# SCH_lab05_2021-12-17_1.net
KiCad netlist of a schematic drawn in EasyEDA
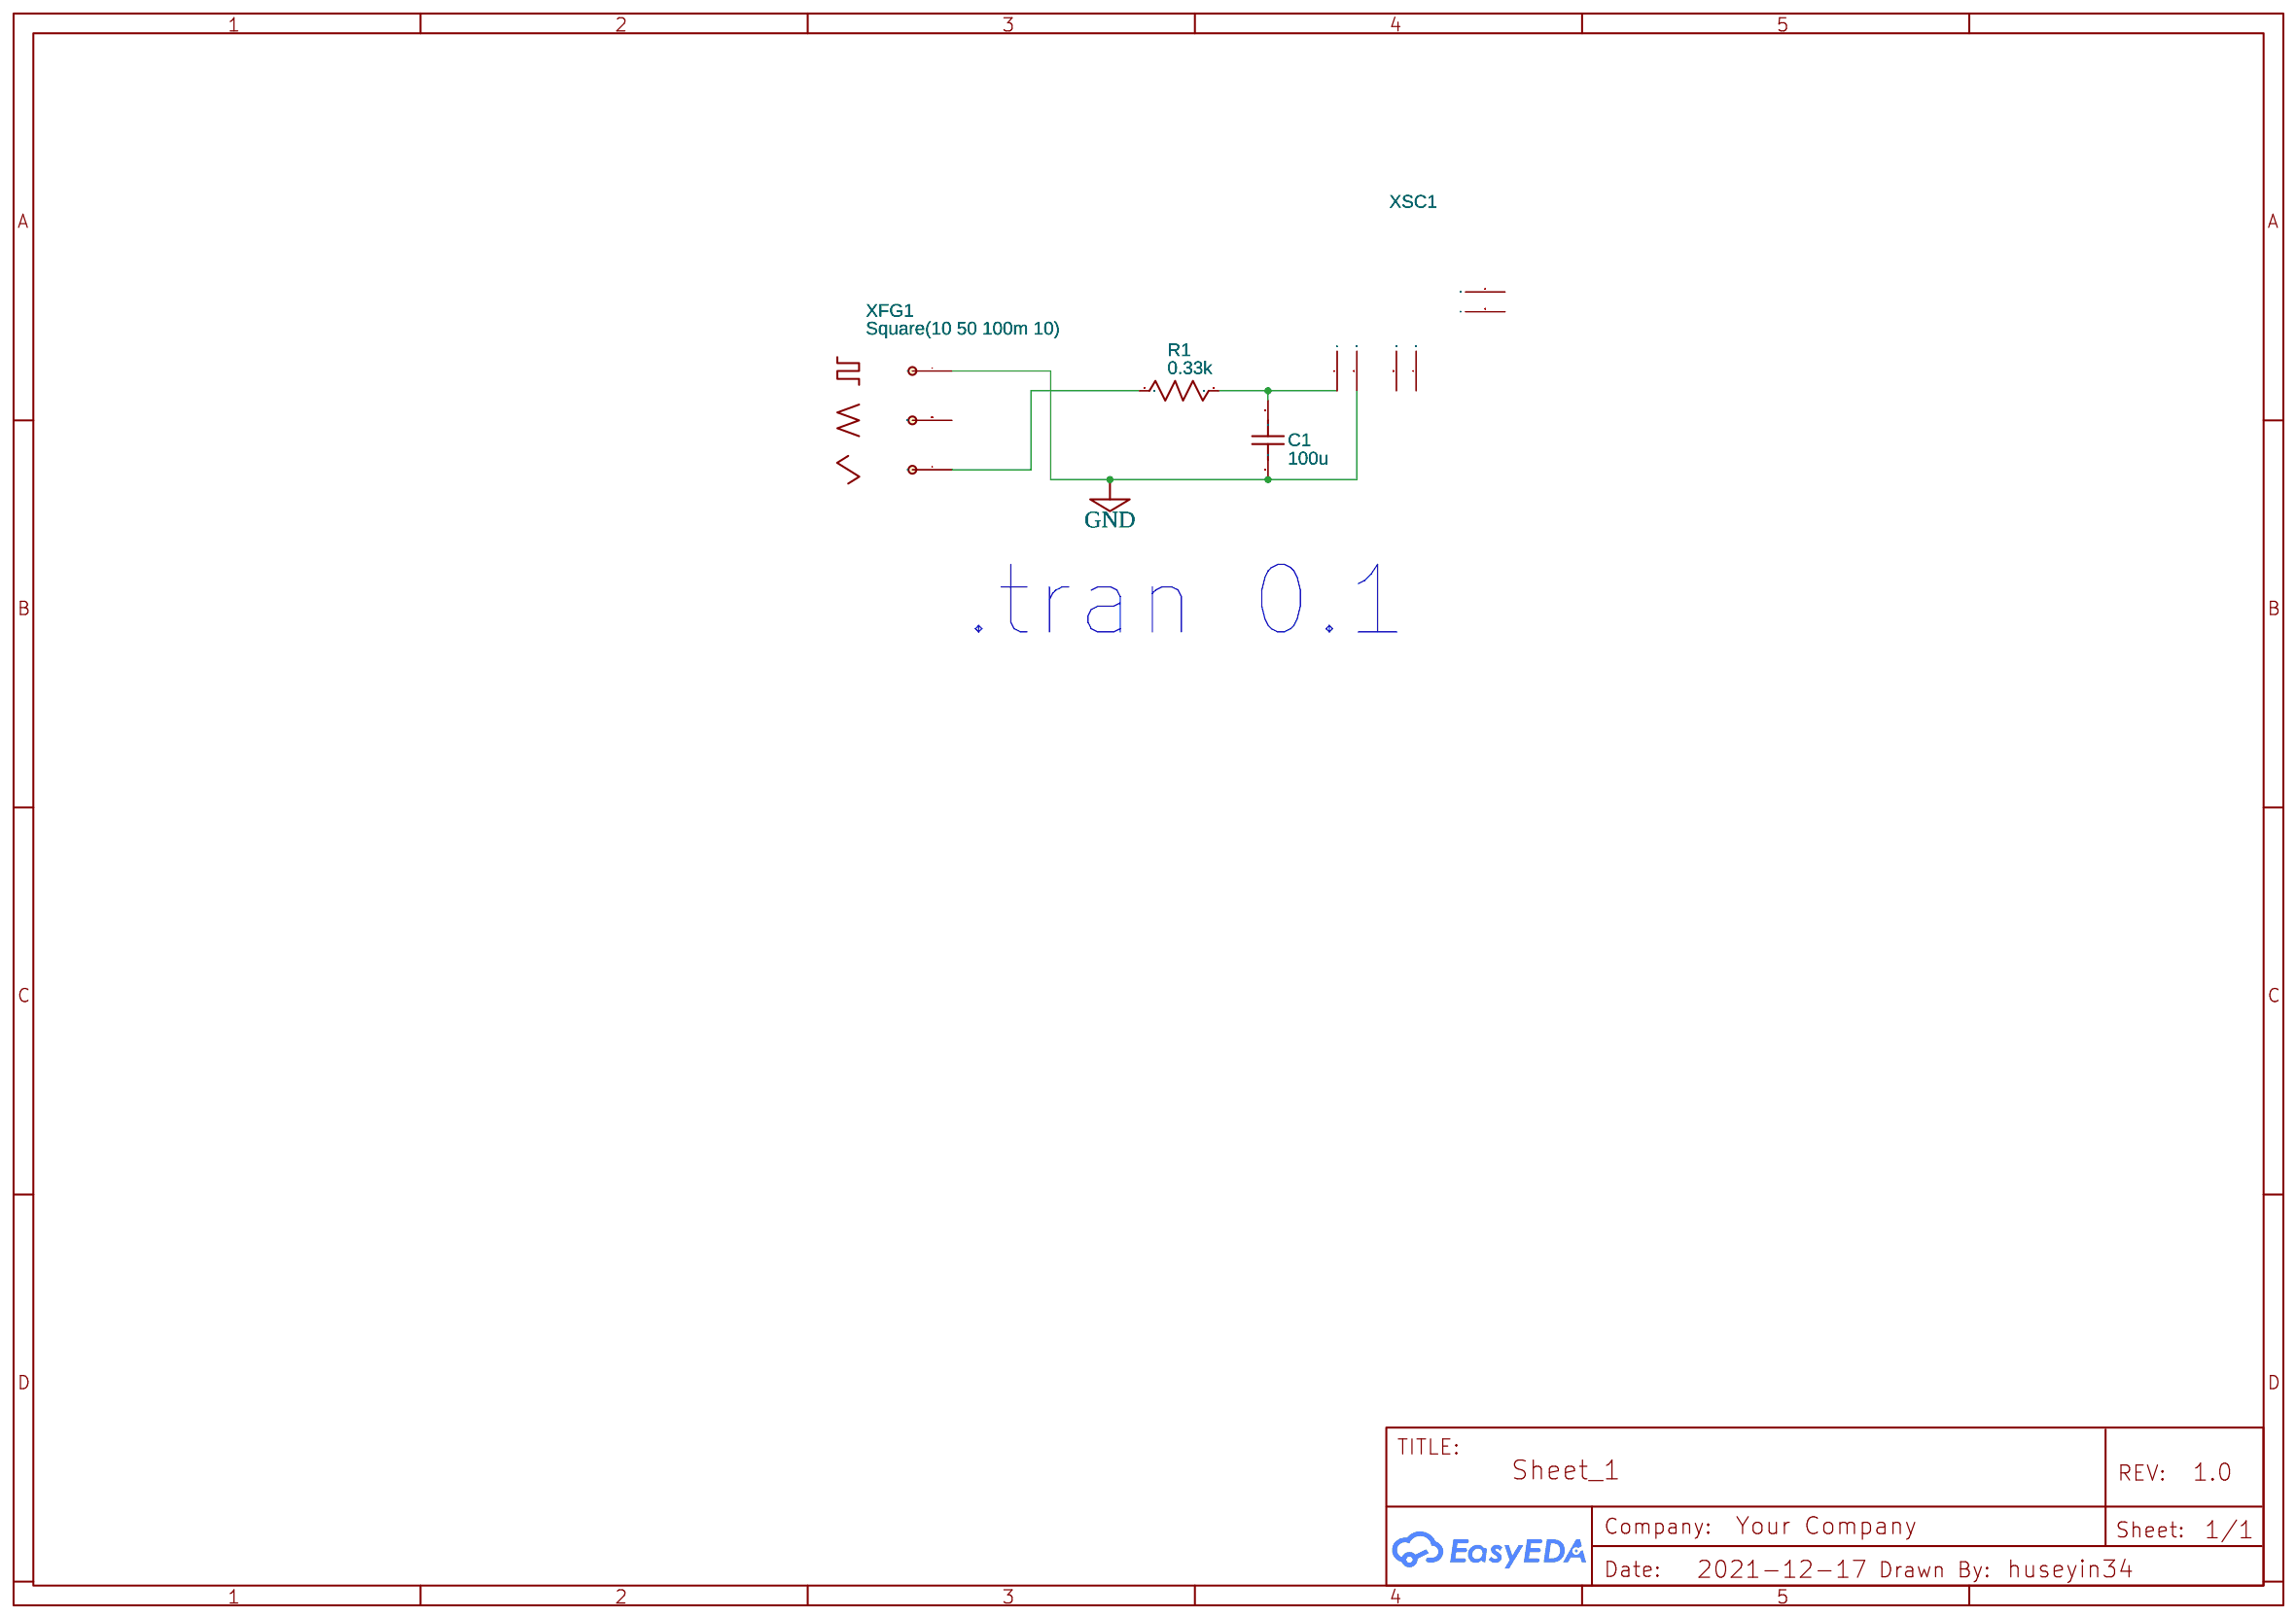
[diagram p0: Sheet_1]
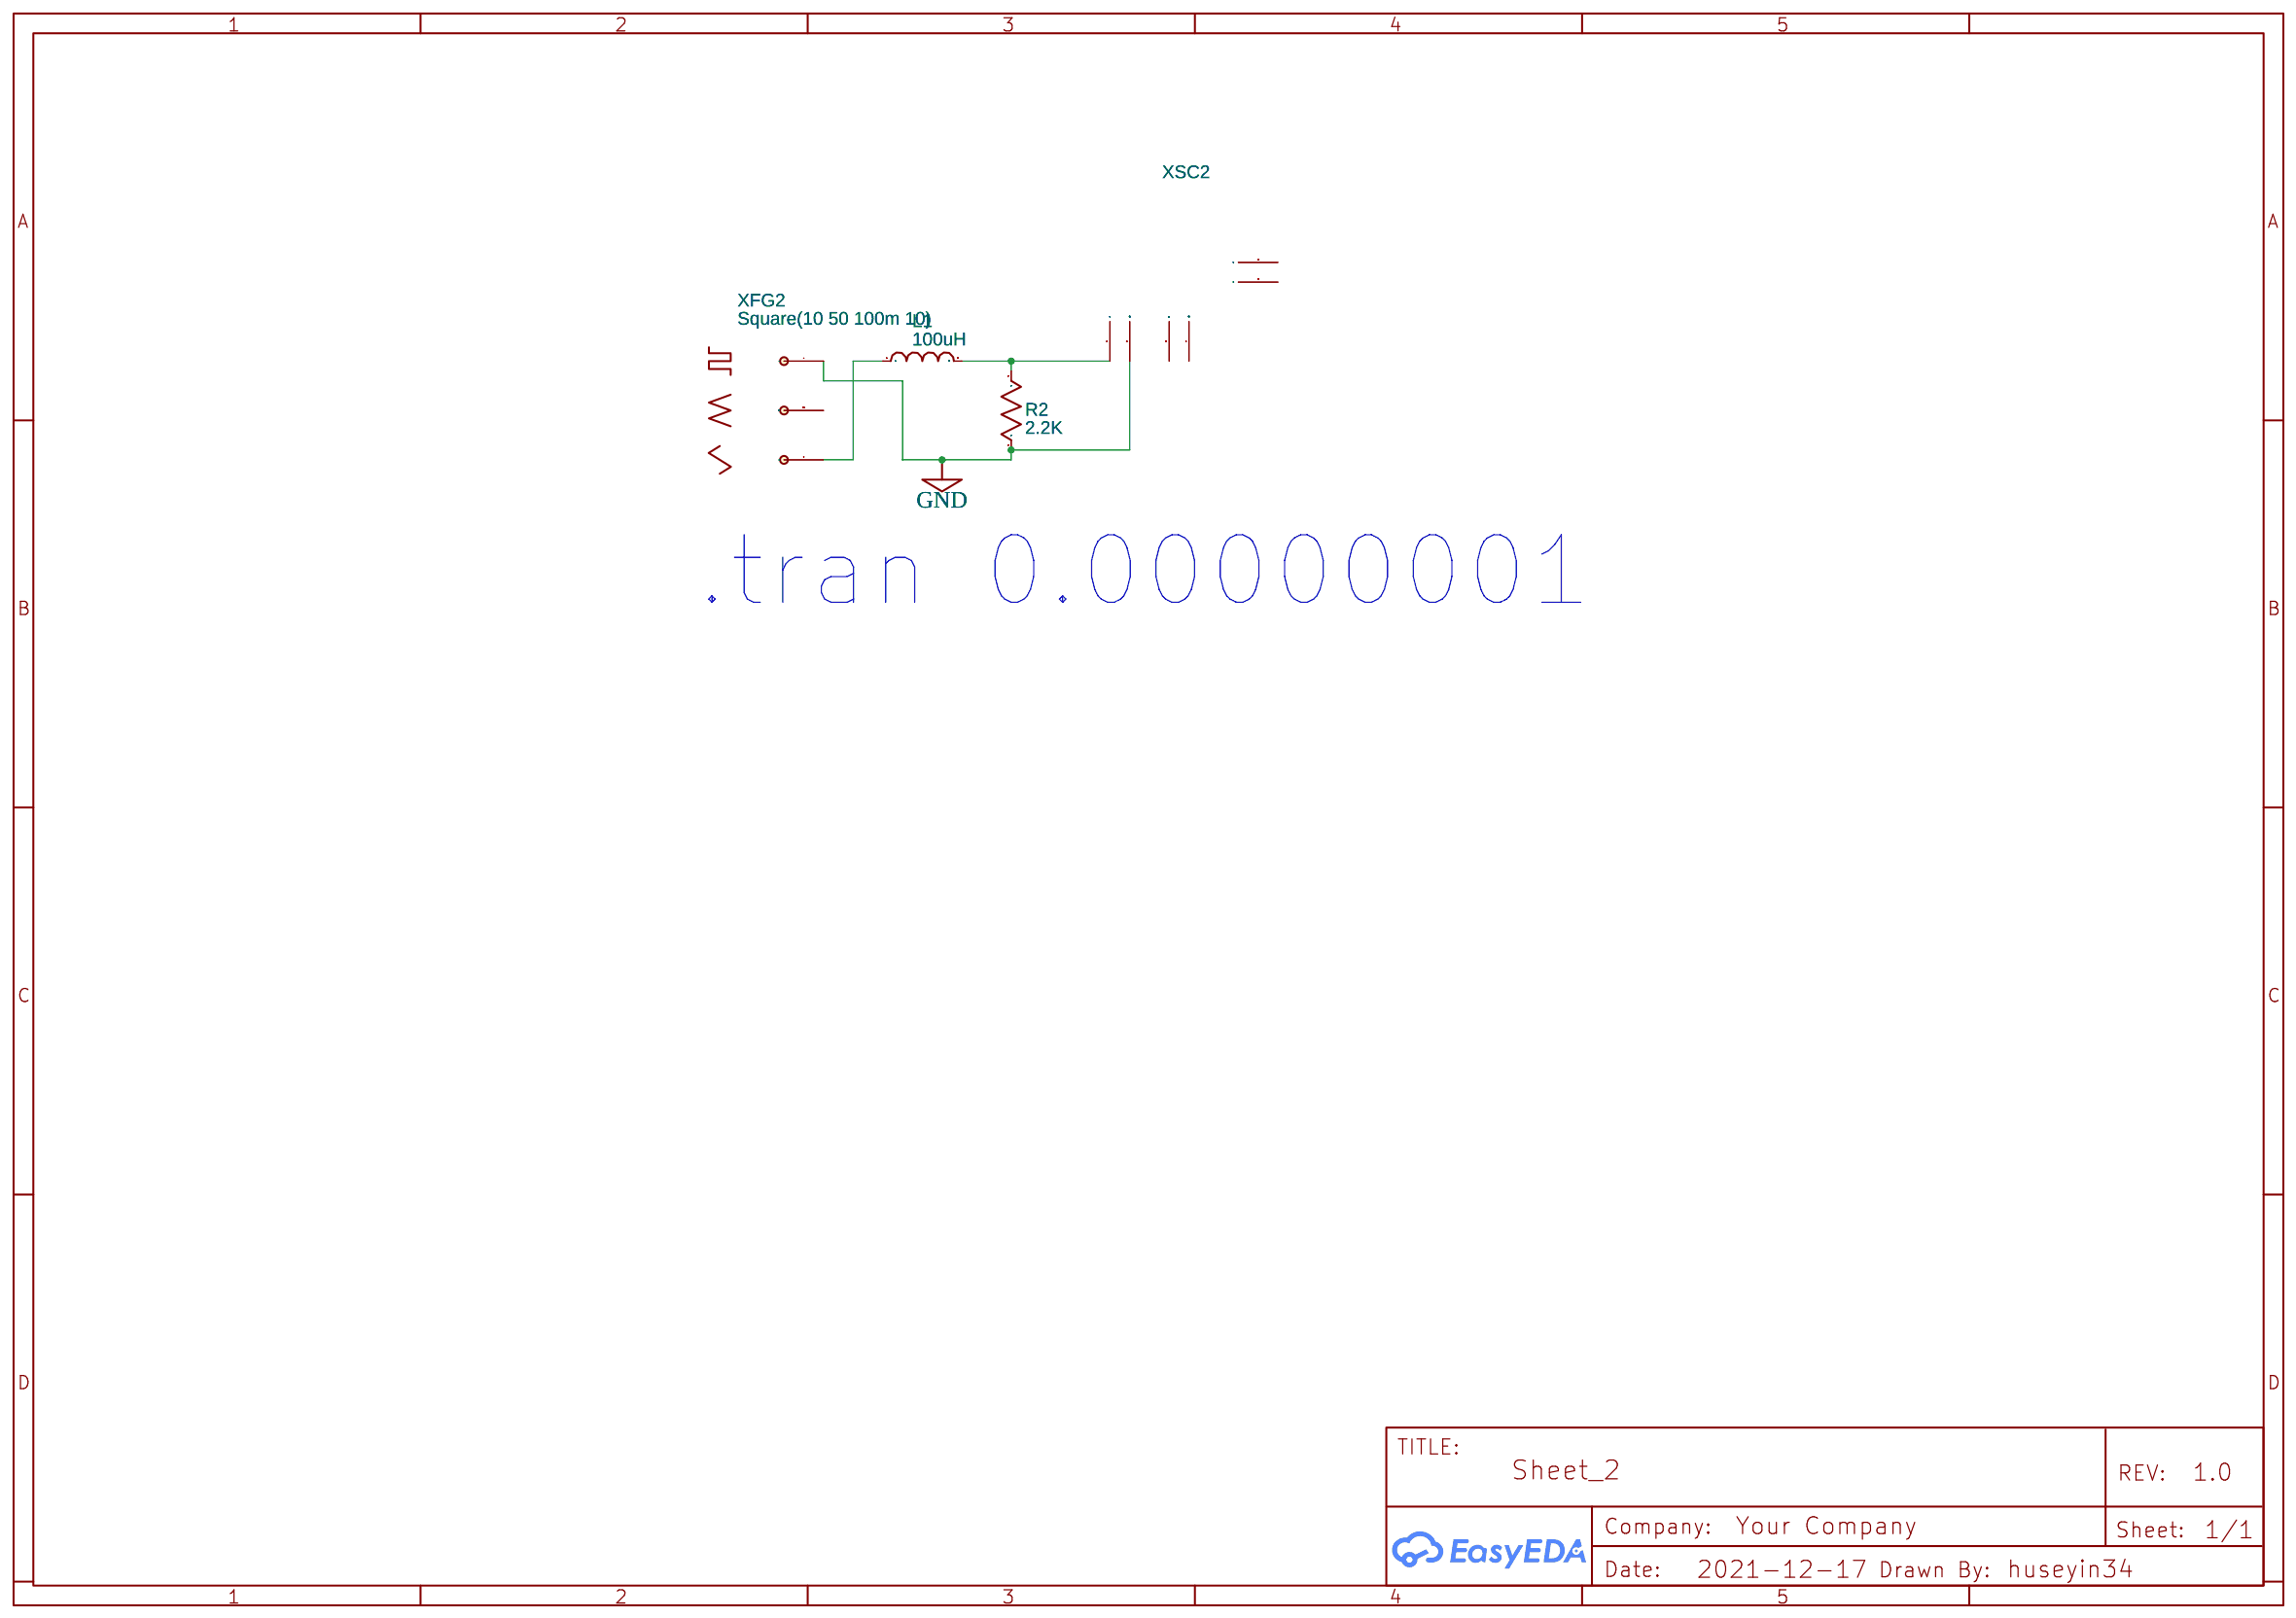
[diagram p1: Sheet_2]
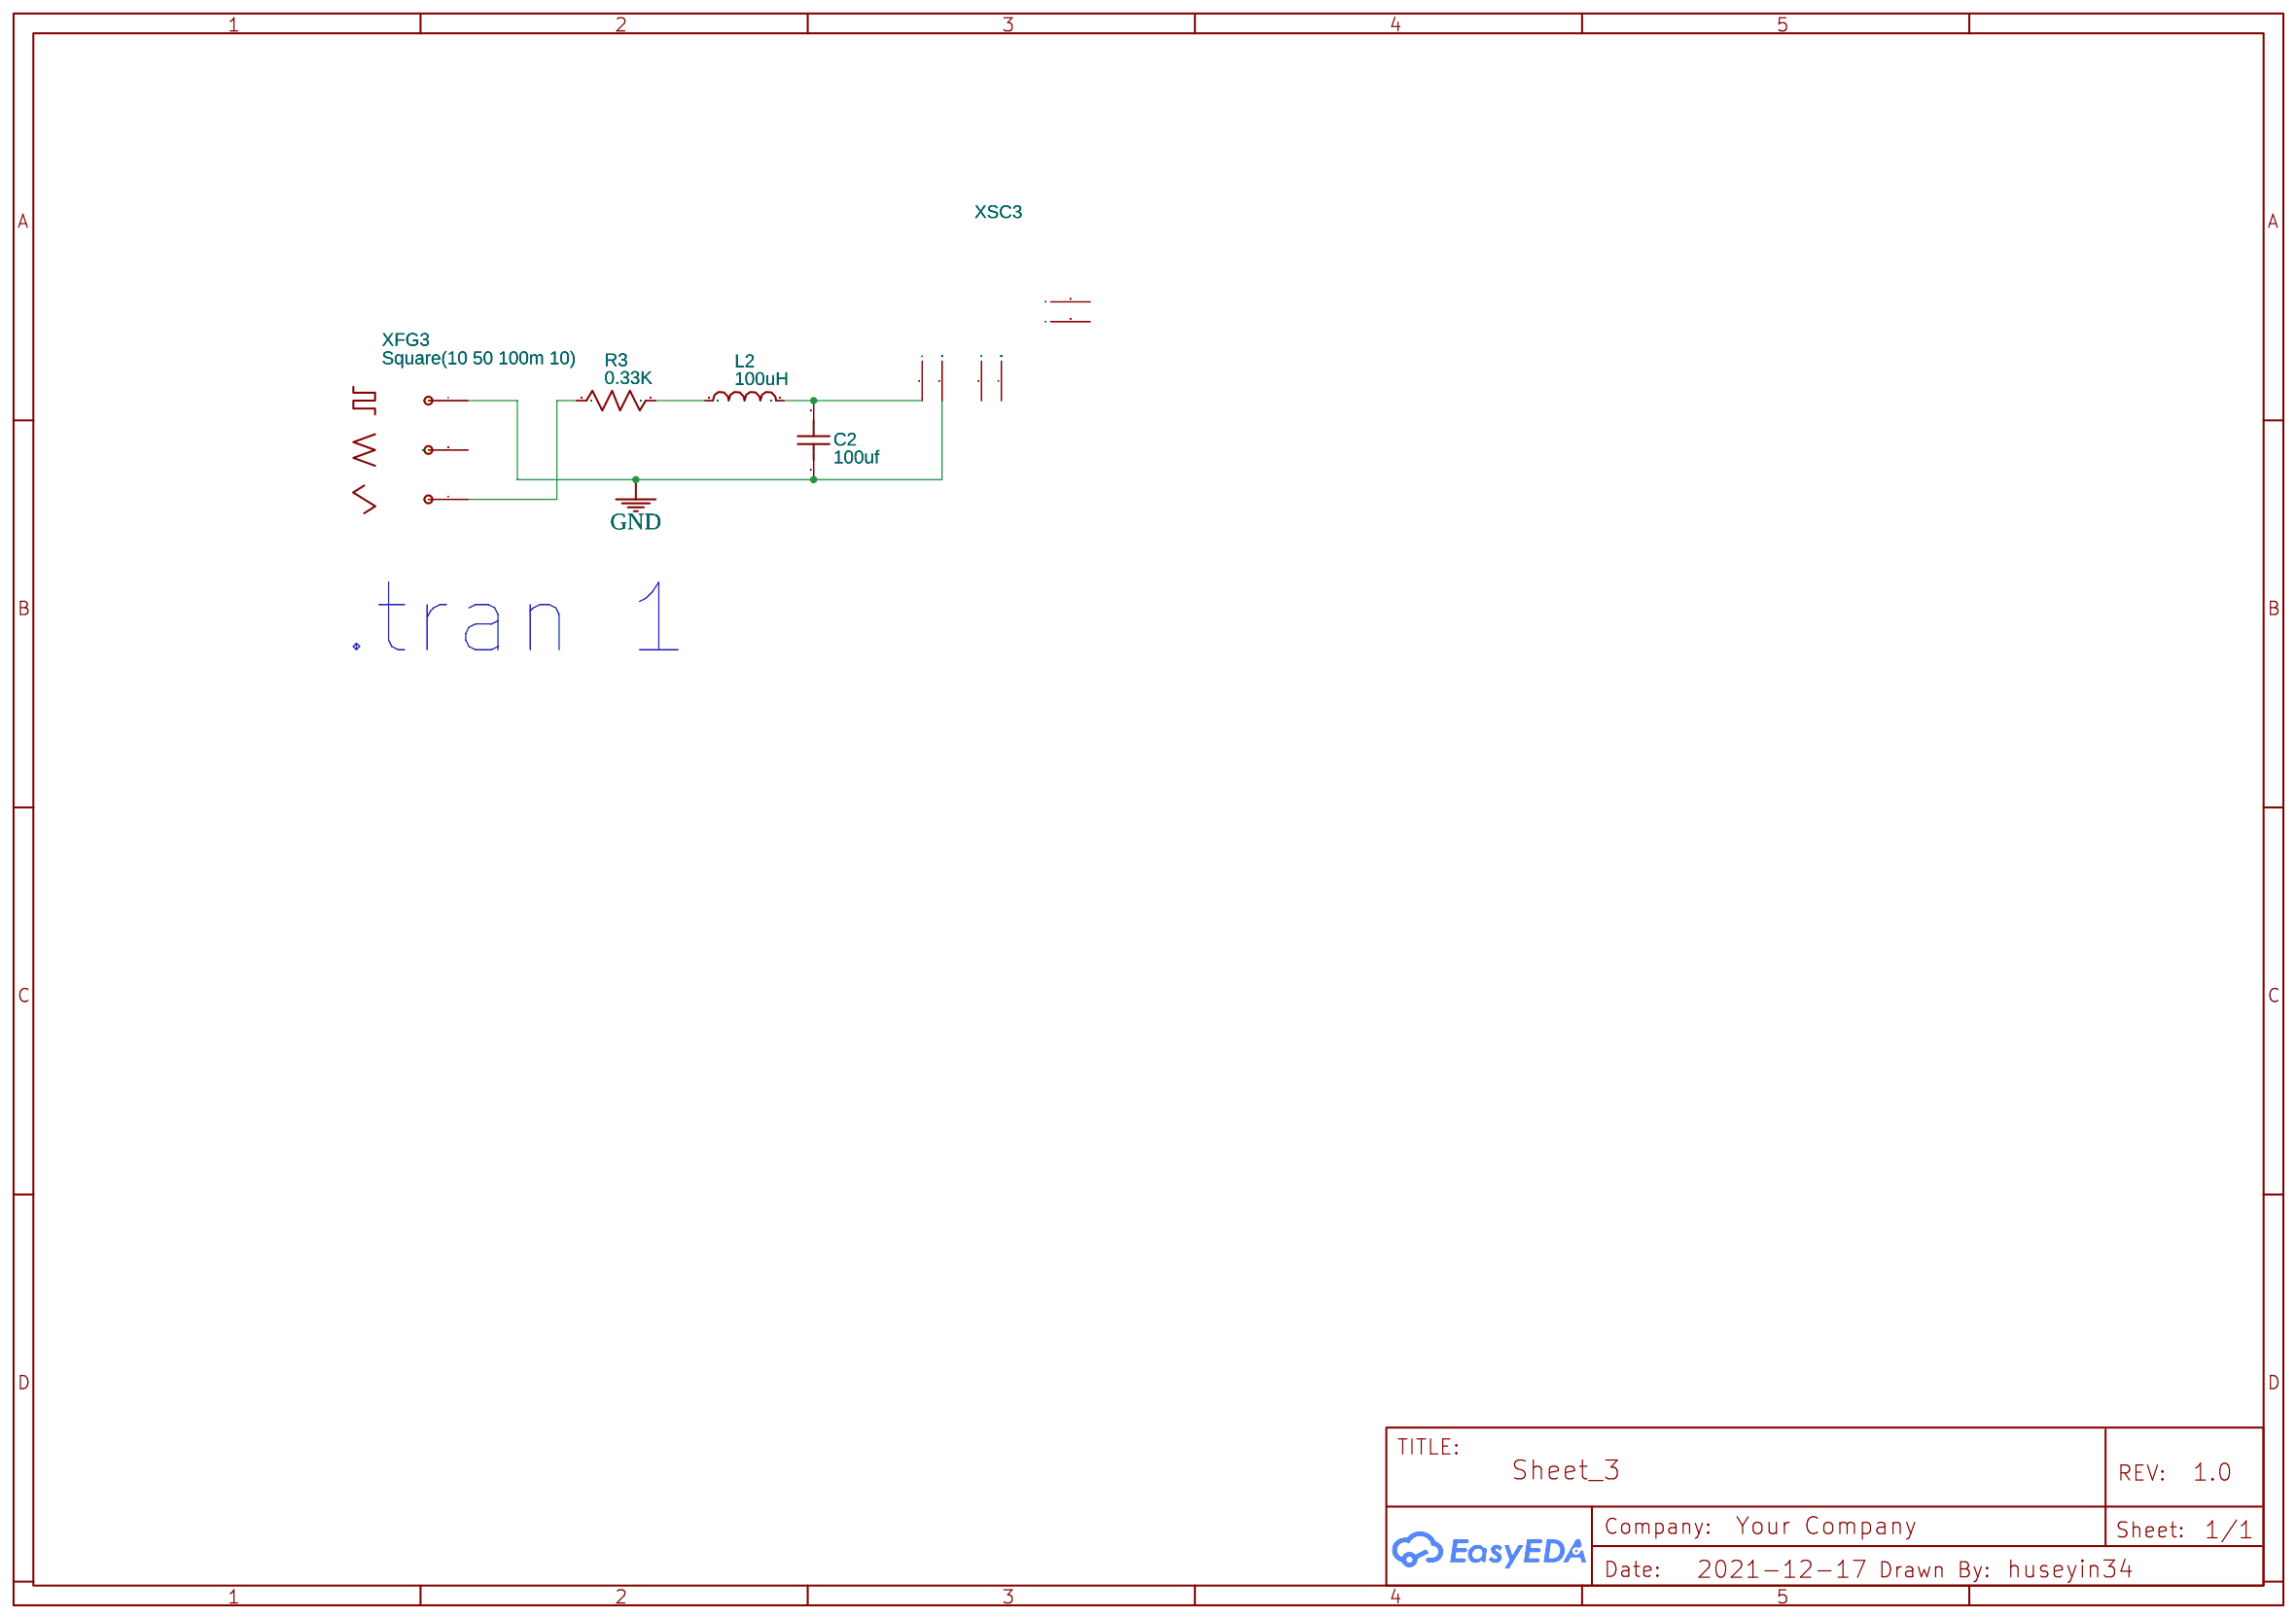
[diagram p2: Sheet_3]

(export (version "E")
  (design (tool "Eeschema 10.0.6"))
  (components
    (comp (ref "C1") (value "100u") (libsource (lib "") (part "Capacitor_US")))
    (comp (ref "R1") (value "0.33k") (libsource (lib "") (part "Resistor_US")))
    (comp (ref "XFG1") (value "Square(10 50 100m 10)") (libsource (lib "") (part "FUNCTIONGENERATOR")))
    (comp (ref "XSC1") (value "Oscilloscope") (libsource (lib "") (part "OSCILLOSCOPE")))
    (comp (ref "L1") (value "100uH") (libsource (lib "") (part "Inductor")))
    (comp (ref "R2") (value "2.2K") (libsource (lib "") (part "Resistor_US")))
    (comp (ref "XFG2") (value "Square(10 50 100m 10)") (libsource (lib "") (part "FUNCTIONGENERATOR")))
    (comp (ref "XSC2") (value "Oscilloscope") (libsource (lib "") (part "OSCILLOSCOPE")))
    (comp (ref "C2") (value "100uf") (libsource (lib "") (part "Capacitor_US")))
    (comp (ref "L2") (value "100uH") (libsource (lib "") (part "Inductor")))
    (comp (ref "R3") (value "0.33K") (libsource (lib "") (part "Resistor_US")))
    (comp (ref "XFG3") (value "Square(10 50 100m 10)") (libsource (lib "") (part "FUNCTIONGENERATOR")))
    (comp (ref "XSC3") (value "Oscilloscope") (libsource (lib "") (part "OSCILLOSCOPE")))
  )
  (nets
    (net (code "1") (name "GND") (class "Default")
      (node (ref "C1") (pin "1") (pinfunction "1_1") (pintype "unspecified"))
      (node (ref "C2") (pin "1") (pinfunction "1_1") (pintype "unspecified"))
      (node (ref "R2") (pin "1") (pinfunction "1_1") (pintype "unspecified"))
      (node (ref "XFG1") (pin "-") (pinfunction "-_-") (pintype "unspecified"))
      (node (ref "XFG2") (pin "-") (pinfunction "-_-") (pintype "unspecified"))
      (node (ref "XFG3") (pin "-") (pinfunction "-_-") (pintype "unspecified"))
      (node (ref "XSC1") (pin "2") (pinfunction "GND1_2") (pintype "unspecified"))
      (node (ref "XSC2") (pin "2") (pinfunction "GND1_2") (pintype "unspecified"))
      (node (ref "XSC3") (pin "2") (pinfunction "GND1_2") (pintype "unspecified"))
    )
    (net (code "2") (name "Net-(L1-Pad1)") (class "Default")
      (node (ref "L1") (pin "1") (pinfunction "1_1") (pintype "unspecified"))
      (node (ref "XFG2") (pin "+") (pinfunction "+_+") (pintype "unspecified"))
    )
    (net (code "3") (name "Net-(L2-Pad1)") (class "Default")
      (node (ref "L2") (pin "1") (pinfunction "1_1") (pintype "unspecified"))
      (node (ref "R3") (pin "2") (pinfunction "2_2") (pintype "unspecified"))
    )
    (net (code "4") (name "Net-(R1-Pad1)") (class "Default")
      (node (ref "R1") (pin "1") (pinfunction "1_1") (pintype "unspecified"))
      (node (ref "XFG1") (pin "+") (pinfunction "+_+") (pintype "unspecified"))
    )
    (net (code "5") (name "Net-(R3-Pad1)") (class "Default")
      (node (ref "R3") (pin "1") (pinfunction "1_1") (pintype "unspecified"))
      (node (ref "XFG3") (pin "+") (pinfunction "+_+") (pintype "unspecified"))
    )
    (net (code "6") (name "Net-(XSC1-A)") (class "Default")
      (node (ref "C1") (pin "2") (pinfunction "2_2") (pintype "unspecified"))
      (node (ref "R1") (pin "2") (pinfunction "2_2") (pintype "unspecified"))
      (node (ref "XSC1") (pin "1") (pinfunction "A_1") (pintype "unspecified"))
    )
    (net (code "7") (name "Net-(XSC2-A)") (class "Default")
      (node (ref "L1") (pin "2") (pinfunction "2_2") (pintype "unspecified"))
      (node (ref "R2") (pin "2") (pinfunction "2_2") (pintype "unspecified"))
      (node (ref "XSC2") (pin "1") (pinfunction "A_1") (pintype "unspecified"))
    )
    (net (code "8") (name "Net-(XSC3-A)") (class "Default")
      (node (ref "C2") (pin "2") (pinfunction "2_2") (pintype "unspecified"))
      (node (ref "L2") (pin "2") (pinfunction "2_2") (pintype "unspecified"))
      (node (ref "XSC3") (pin "1") (pinfunction "A_1") (pintype "unspecified"))
    )
    (net (code "9") (name "unconnected-(XFG1-PadCOM)") (class "Default")
      (node (ref "XFG1") (pin "COM") (pinfunction "COM_COM") (pintype "unspecified"))
    )
    (net (code "10") (name "unconnected-(XFG2-PadCOM)") (class "Default")
      (node (ref "XFG2") (pin "COM") (pinfunction "COM_COM") (pintype "unspecified"))
    )
    (net (code "11") (name "unconnected-(XFG3-PadCOM)") (class "Default")
      (node (ref "XFG3") (pin "COM") (pinfunction "COM_COM") (pintype "unspecified"))
    )
    (net (code "12") (name "unconnected-(XSC1-B-Pad3)") (class "Default")
      (node (ref "XSC1") (pin "3") (pinfunction "B_3") (pintype "unspecified"))
    )
    (net (code "13") (name "unconnected-(XSC1-GND2-Pad4)") (class "Default")
      (node (ref "XSC1") (pin "4") (pinfunction "GND2_4") (pintype "unspecified"))
    )
    (net (code "14") (name "unconnected-(XSC1-T+-Pad5)") (class "Default")
      (node (ref "XSC1") (pin "5") (pinfunction "T+_5") (pintype "unspecified"))
    )
    (net (code "15") (name "unconnected-(XSC1-T--Pad6)") (class "Default")
      (node (ref "XSC1") (pin "6") (pinfunction "T-_6") (pintype "unspecified"))
    )
    (net (code "16") (name "unconnected-(XSC2-B-Pad3)") (class "Default")
      (node (ref "XSC2") (pin "3") (pinfunction "B_3") (pintype "unspecified"))
    )
    (net (code "17") (name "unconnected-(XSC2-GND2-Pad4)") (class "Default")
      (node (ref "XSC2") (pin "4") (pinfunction "GND2_4") (pintype "unspecified"))
    )
    (net (code "18") (name "unconnected-(XSC2-T+-Pad5)") (class "Default")
      (node (ref "XSC2") (pin "5") (pinfunction "T+_5") (pintype "unspecified"))
    )
    (net (code "19") (name "unconnected-(XSC2-T--Pad6)") (class "Default")
      (node (ref "XSC2") (pin "6") (pinfunction "T-_6") (pintype "unspecified"))
    )
    (net (code "20") (name "unconnected-(XSC3-B-Pad3)") (class "Default")
      (node (ref "XSC3") (pin "3") (pinfunction "B_3") (pintype "unspecified"))
    )
    (net (code "21") (name "unconnected-(XSC3-GND2-Pad4)") (class "Default")
      (node (ref "XSC3") (pin "4") (pinfunction "GND2_4") (pintype "unspecified"))
    )
    (net (code "22") (name "unconnected-(XSC3-T+-Pad5)") (class "Default")
      (node (ref "XSC3") (pin "5") (pinfunction "T+_5") (pintype "unspecified"))
    )
    (net (code "23") (name "unconnected-(XSC3-T--Pad6)") (class "Default")
      (node (ref "XSC3") (pin "6") (pinfunction "T-_6") (pintype "unspecified"))
    )
  )
)
